# DCDC_ACCUMULATOR.net
KiCad netlist of a schematic drawn in EAGLE
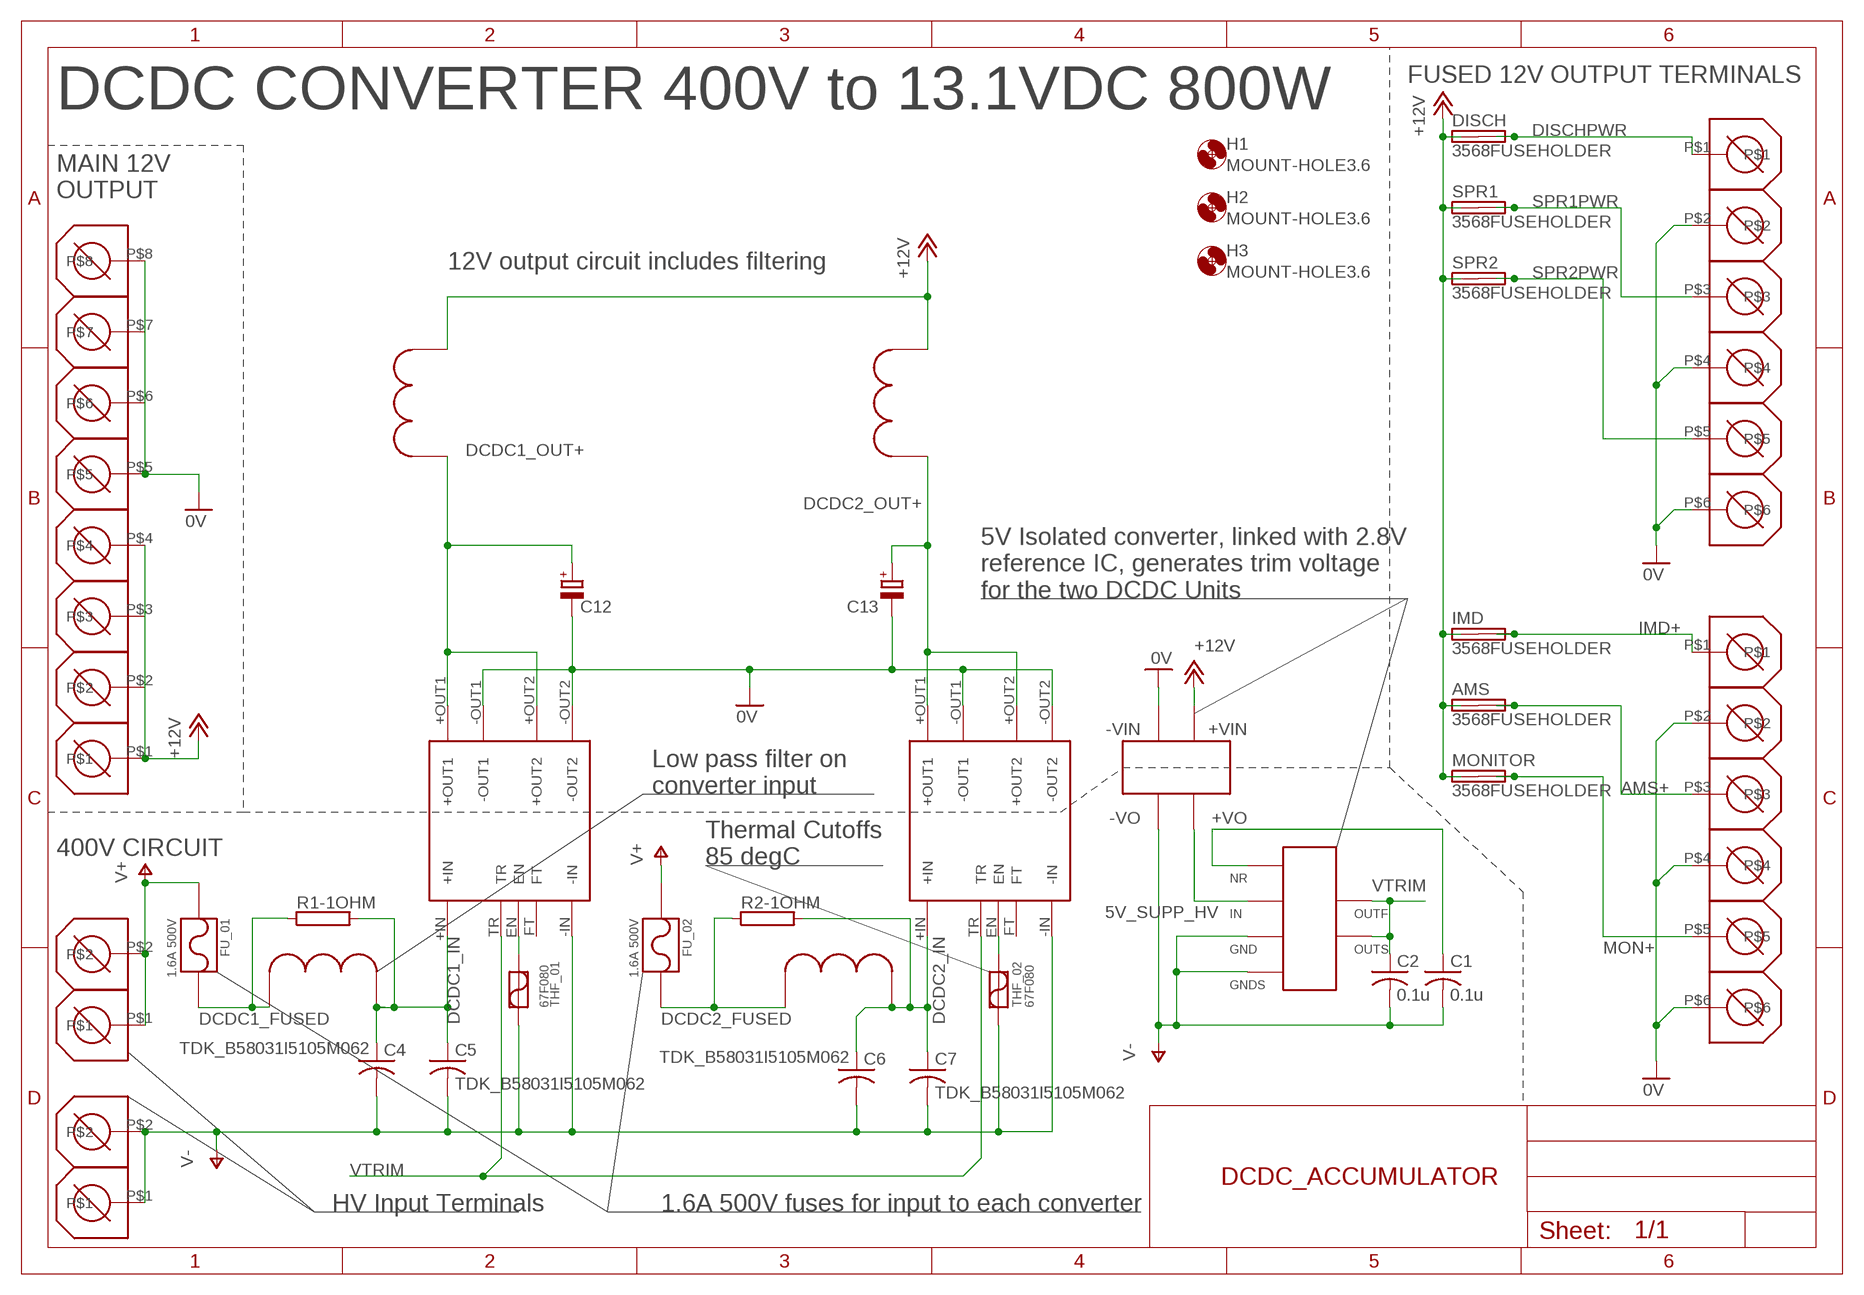
[diagram p0: schematic, sheet 1]

(export (version "E")
  (design (tool "Eeschema 10.0.6"))
  (components
    (comp (ref "AMS")
      (value "3568FUSEHOLDER")
      (footprint "eagle-import:3568")
      (libsource (lib "eagle-import") (part "3568FUSEHOLDER"))
    )
    (comp (ref "C1")
      (value "0.1u")
      (footprint "eagle-import:C0805")
      (libsource (lib "eagle-import") (part "C-USC0805"))
    )
    (comp (ref "C2")
      (value "0.1u")
      (footprint "eagle-import:C0805")
      (libsource (lib "eagle-import") (part "C-USC0805"))
    )
    (comp (ref "C4")
      (value "TDK_B58031I5105M062")
      (footprint "eagle-import:TDK_CERALINK_USTYLE")
      (libsource (lib "eagle-import") (part "TDK_B58031I5105M062"))
    )
    (comp (ref "C5")
      (value "TDK_B58031I5105M062")
      (footprint "eagle-import:TDK_CERALINK_USTYLE")
      (libsource (lib "eagle-import") (part "TDK_B58031I5105M062"))
    )
    (comp (ref "C6")
      (value "TDK_B58031I5105M062")
      (footprint "eagle-import:TDK_CERALINK_USTYLE")
      (libsource (lib "eagle-import") (part "TDK_B58031I5105M062"))
    )
    (comp (ref "C7")
      (value "TDK_B58031I5105M062")
      (footprint "eagle-import:TDK_CERALINK_USTYLE")
      (libsource (lib "eagle-import") (part "TDK_B58031I5105M062"))
    )
    (comp (ref "C12")
      (value "CPOL-EUE7.5-16")
      (footprint "eagle-import:E7,5-16")
      (libsource (lib "eagle-import") (part "CPOL-EUE7.5-16"))
    )
    (comp (ref "C13")
      (value "CPOL-EUE7.5-16")
      (footprint "eagle-import:E7,5-16")
      (libsource (lib "eagle-import") (part "CPOL-EUE7.5-16"))
    )
    (comp (ref "DISCH")
      (value "3568FUSEHOLDER")
      (footprint "eagle-import:3568")
      (libsource (lib "eagle-import") (part "3568FUSEHOLDER"))
    )
    (comp (ref "FU_01")
      (value "1.6A 500V")
      (footprint "eagle-import:LF_885")
      (libsource (lib "eagle-import") (part "LF_885"))
    )
    (comp (ref "FU_02")
      (value "1.6A 500V")
      (footprint "eagle-import:LF_885")
      (libsource (lib "eagle-import") (part "LF_885"))
    )
    (comp (ref "H1")
      (value "MOUNT-HOLE3.6")
      (footprint "eagle-import:3,6")
      (libsource (lib "eagle-import") (part "MOUNT-HOLE3.6"))
    )
    (comp (ref "H2")
      (value "MOUNT-HOLE3.6")
      (footprint "eagle-import:3,6")
      (libsource (lib "eagle-import") (part "MOUNT-HOLE3.6"))
    )
    (comp (ref "H3")
      (value "MOUNT-HOLE3.6")
      (footprint "eagle-import:3,6")
      (libsource (lib "eagle-import") (part "MOUNT-HOLE3.6"))
    )
    (comp (ref "IMD")
      (value "3568FUSEHOLDER")
      (footprint "eagle-import:3568")
      (libsource (lib "eagle-import") (part "3568FUSEHOLDER"))
    )
    (comp (ref "MONITOR")
      (value "3568FUSEHOLDER")
      (footprint "eagle-import:3568")
      (libsource (lib "eagle-import") (part "3568FUSEHOLDER"))
    )
    (comp (ref "R1-1OHM")
      (value "RMG100-V")
      (footprint "eagle-import:TO-247-2V")
      (libsource (lib "eagle-import") (part "RMG100-V"))
    )
    (comp (ref "R2-1OHM")
      (value "RMG100-V")
      (footprint "eagle-import:TO-247-2V")
      (libsource (lib "eagle-import") (part "RMG100-V"))
    )
    (comp (ref "SPR1")
      (value "3568FUSEHOLDER")
      (footprint "eagle-import:3568")
      (libsource (lib "eagle-import") (part "3568FUSEHOLDER"))
    )
    (comp (ref "SPR2")
      (value "3568FUSEHOLDER")
      (footprint "eagle-import:3568")
      (libsource (lib "eagle-import") (part "3568FUSEHOLDER"))
    )
    (comp (ref "THF_01")
      (value "67F080")
      (footprint "eagle-import:TO220ACS")
      (libsource (lib "eagle-import") (part "67F080"))
    )
    (comp (ref "THF_02")
      (value "67F080")
      (footprint "eagle-import:TO220ACS")
      (libsource (lib "eagle-import") (part "67F080"))
    )
    (comp (ref "U$1")
      (value "DCM4623TD2J13D0T00")
      (footprint "eagle-import:VICOR_DCM4623TD2J13D0T00")
      (libsource (lib "eagle-import") (part "DCM4623TD2J13D0T00"))
    )
    (comp (ref "U$2")
      (value "P1330-102H")
      (footprint "eagle-import:P1330")
      (libsource (lib "eagle-import") (part "P1330-102H"))
    )
    (comp (ref "U$3")
      (value "MPC1250LR36C")
      (footprint "eagle-import:MPC1250LR")
      (libsource (lib "eagle-import") (part "MPC1250LR36C"))
    )
    (comp (ref "U$4")
      (value "DCM4623TD2J13D0T00")
      (footprint "eagle-import:VICOR_DCM4623TD2J13D0T00")
      (libsource (lib "eagle-import") (part "DCM4623TD2J13D0T00"))
    )
    (comp (ref "U$5")
      (value "P1330-102H")
      (footprint "eagle-import:P1330")
      (libsource (lib "eagle-import") (part "P1330-102H"))
    )
    (comp (ref "U$6")
      (value "MPC1250LR36C")
      (footprint "eagle-import:MPC1250LR")
      (libsource (lib "eagle-import") (part "MPC1250LR36C"))
    )
    (comp (ref "U$9")
      (value "MURATA_MEV1S1205SC")
      (footprint "eagle-import:MEV_7_PIN_SIP")
      (libsource (lib "eagle-import") (part "MURATA_MEV1S1205SC"))
    )
    (comp (ref "U$10")
      (value "MAXIM_MAX6126A28")
      (footprint "eagle-import:UMAX")
      (libsource (lib "eagle-import") (part "MAXIM_MAX6126A28"))
    )
    (comp (ref "U$13")
      (value "1777600_PHOENIX")
      (footprint "eagle-import:1777600_FOOT")
      (libsource (lib "eagle-import") (part "1777600_PHOENIX"))
    )
    (comp (ref "U$14")
      (value "1935200_PHOENIX")
      (footprint "eagle-import:1777587_FOOT")
      (libsource (lib "eagle-import") (part "1935200_PHOENIX"))
    )
    (comp (ref "U$15")
      (value "1935200_PHOENIX")
      (footprint "eagle-import:1777587_FOOT")
      (libsource (lib "eagle-import") (part "1935200_PHOENIX"))
    )
    (comp (ref "U$16")
      (value "282838-2_TE")
      (footprint "eagle-import:282838-2_FOOT")
      (libsource (lib "eagle-import") (part "282838-2_TE"))
    )
    (comp (ref "U$17")
      (value "282838-2_TE")
      (footprint "eagle-import:282838-2_FOOT")
      (libsource (lib "eagle-import") (part "282838-2_TE"))
    )
  )
  (nets
    (net (code "1") (name "+12V") (class "Default")
      (node (ref "AMS") (pin "L1") (pinfunction "1A_L1") (pintype "passive"))
      (node (ref "AMS") (pin "L2") (pinfunction "1B_L2") (pintype "passive"))
      (node (ref "DISCH") (pin "L1") (pinfunction "1A_L1") (pintype "passive"))
      (node (ref "DISCH") (pin "L2") (pinfunction "1B_L2") (pintype "passive"))
      (node (ref "IMD") (pin "L1") (pinfunction "1A_L1") (pintype "passive"))
      (node (ref "IMD") (pin "L2") (pinfunction "1B_L2") (pintype "passive"))
      (node (ref "MONITOR") (pin "L1") (pinfunction "1A_L1") (pintype "passive"))
      (node (ref "MONITOR") (pin "L2") (pinfunction "1B_L2") (pintype "passive"))
      (node (ref "SPR1") (pin "L1") (pinfunction "1A_L1") (pintype "passive"))
      (node (ref "SPR1") (pin "L2") (pinfunction "1B_L2") (pintype "passive"))
      (node (ref "SPR2") (pin "L1") (pinfunction "1A_L1") (pintype "passive"))
      (node (ref "SPR2") (pin "L2") (pinfunction "1B_L2") (pintype "passive"))
      (node (ref "U$13") (pin "P$1") (pinfunction "P$1_P$1") (pintype "bidirectional"))
      (node (ref "U$13") (pin "P$2") (pinfunction "P$2_P$2") (pintype "bidirectional"))
      (node (ref "U$13") (pin "P$3") (pinfunction "P$3_P$3") (pintype "bidirectional"))
      (node (ref "U$13") (pin "P$4") (pinfunction "P$4_P$4") (pintype "bidirectional"))
      (node (ref "U$3") (pin "P$2") (pinfunction "P$2_P$2") (pintype "bidirectional"))
      (node (ref "U$6") (pin "P$2") (pinfunction "P$2_P$2") (pintype "bidirectional"))
      (node (ref "U$9") (pin "+VIN") (pinfunction "+VIN_+VIN") (pintype "bidirectional"))
    )
    (net (code "2") (name "/5V_SUPP_HV") (class "Default")
      (node (ref "U$10") (pin "2") (pinfunction "IN_2") (pintype "bidirectional"))
      (node (ref "U$9") (pin "+VOUT") (pinfunction "+VO_+VOUT") (pintype "bidirectional"))
    )
    (net (code "3") (name "/AMS+") (class "Default")
      (node (ref "AMS") (pin "R1") (pinfunction "2A_R1") (pintype "passive"))
      (node (ref "AMS") (pin "R2") (pinfunction "2B_R2") (pintype "passive"))
      (node (ref "U$15") (pin "P$3") (pinfunction "P$3_P$3") (pintype "bidirectional"))
    )
    (net (code "4") (name "/DCDC1_FUSED") (class "Default")
      (node (ref "FU_01") (pin "P$2") (pinfunction "P$2_P$2") (pintype "bidirectional"))
      (node (ref "R1-1OHM") (pin "1") (pinfunction "1_1") (pintype "passive"))
      (node (ref "U$2") (pin "P$1") (pinfunction "P$1_P$1") (pintype "bidirectional"))
    )
    (net (code "5") (name "/DCDC1_IN") (class "Default")
      (node (ref "C4") (pin "P$1") (pinfunction "1_P$1") (pintype "passive"))
      (node (ref "C5") (pin "P$1") (pinfunction "1_P$1") (pintype "passive"))
      (node (ref "R1-1OHM") (pin "2") (pinfunction "2_2") (pintype "passive"))
      (node (ref "U$1") (pin "+IN") (pinfunction "+IN_+IN") (pintype "bidirectional"))
      (node (ref "U$2") (pin "P$2") (pinfunction "P$2_P$2") (pintype "bidirectional"))
    )
    (net (code "6") (name "/DCDC1_OUT+") (class "Default")
      (node (ref "C12") (pin "+") (pinfunction "+_+") (pintype "passive"))
      (node (ref "U$1") (pin "+OUT1") (pinfunction "+OUT1_+OUT1") (pintype "bidirectional"))
      (node (ref "U$1") (pin "+OUT2") (pinfunction "+OUT2_+OUT2") (pintype "bidirectional"))
      (node (ref "U$3") (pin "P$1") (pinfunction "P$1_P$1") (pintype "bidirectional"))
    )
    (net (code "7") (name "/DCDC2_FUSED") (class "Default")
      (node (ref "FU_02") (pin "P$2") (pinfunction "P$2_P$2") (pintype "bidirectional"))
      (node (ref "R2-1OHM") (pin "1") (pinfunction "1_1") (pintype "passive"))
      (node (ref "U$5") (pin "P$1") (pinfunction "P$1_P$1") (pintype "bidirectional"))
    )
    (net (code "8") (name "/DCDC2_IN") (class "Default")
      (node (ref "C6") (pin "P$1") (pinfunction "1_P$1") (pintype "passive"))
      (node (ref "C7") (pin "P$1") (pinfunction "1_P$1") (pintype "passive"))
      (node (ref "R2-1OHM") (pin "2") (pinfunction "2_2") (pintype "passive"))
      (node (ref "U$4") (pin "+IN") (pinfunction "+IN_+IN") (pintype "bidirectional"))
      (node (ref "U$5") (pin "P$2") (pinfunction "P$2_P$2") (pintype "bidirectional"))
    )
    (net (code "9") (name "/DCDC2_OUT+") (class "Default")
      (node (ref "C13") (pin "+") (pinfunction "+_+") (pintype "passive"))
      (node (ref "U$4") (pin "+OUT1") (pinfunction "+OUT1_+OUT1") (pintype "bidirectional"))
      (node (ref "U$4") (pin "+OUT2") (pinfunction "+OUT2_+OUT2") (pintype "bidirectional"))
      (node (ref "U$6") (pin "P$1") (pinfunction "P$1_P$1") (pintype "bidirectional"))
    )
    (net (code "10") (name "/DISCHPWR") (class "Default")
      (node (ref "DISCH") (pin "R1") (pinfunction "2A_R1") (pintype "passive"))
      (node (ref "DISCH") (pin "R2") (pinfunction "2B_R2") (pintype "passive"))
      (node (ref "U$14") (pin "P$1") (pinfunction "P$1_P$1") (pintype "bidirectional"))
    )
    (net (code "11") (name "/IMD+") (class "Default")
      (node (ref "IMD") (pin "R1") (pinfunction "2A_R1") (pintype "passive"))
      (node (ref "IMD") (pin "R2") (pinfunction "2B_R2") (pintype "passive"))
      (node (ref "U$15") (pin "P$1") (pinfunction "P$1_P$1") (pintype "bidirectional"))
    )
    (net (code "12") (name "/MON+") (class "Default")
      (node (ref "MONITOR") (pin "R1") (pinfunction "2A_R1") (pintype "passive"))
      (node (ref "MONITOR") (pin "R2") (pinfunction "2B_R2") (pintype "passive"))
      (node (ref "U$15") (pin "P$5") (pinfunction "P$5_P$5") (pintype "bidirectional"))
    )
    (net (code "13") (name "/SPR1PWR") (class "Default")
      (node (ref "SPR1") (pin "R1") (pinfunction "2A_R1") (pintype "passive"))
      (node (ref "SPR1") (pin "R2") (pinfunction "2B_R2") (pintype "passive"))
      (node (ref "U$14") (pin "P$3") (pinfunction "P$3_P$3") (pintype "bidirectional"))
    )
    (net (code "14") (name "/SPR2PWR") (class "Default")
      (node (ref "SPR2") (pin "R1") (pinfunction "2A_R1") (pintype "passive"))
      (node (ref "SPR2") (pin "R2") (pinfunction "2B_R2") (pintype "passive"))
      (node (ref "U$14") (pin "P$5") (pinfunction "P$5_P$5") (pintype "bidirectional"))
    )
    (net (code "15") (name "/VTRIM") (class "Default")
      (node (ref "C2") (pin "1") (pinfunction "1_1") (pintype "passive"))
      (node (ref "U$1") (pin "TR") (pinfunction "TR_TR") (pintype "bidirectional"))
      (node (ref "U$10") (pin "6") (pinfunction "OUTS_6") (pintype "bidirectional"))
      (node (ref "U$10") (pin "7") (pinfunction "OUTF_7") (pintype "bidirectional"))
      (node (ref "U$4") (pin "TR") (pinfunction "TR_TR") (pintype "bidirectional"))
    )
    (net (code "16") (name "0V") (class "Default")
      (node (ref "C12") (pin "-") (pinfunction "-_-") (pintype "passive"))
      (node (ref "C13") (pin "-") (pinfunction "-_-") (pintype "passive"))
      (node (ref "U$1") (pin "-OUT1") (pinfunction "-OUT1_-OUT1") (pintype "bidirectional"))
      (node (ref "U$1") (pin "-OUT2") (pinfunction "-OUT2_-OUT2") (pintype "bidirectional"))
      (node (ref "U$13") (pin "P$5") (pinfunction "P$5_P$5") (pintype "bidirectional"))
      (node (ref "U$13") (pin "P$6") (pinfunction "P$6_P$6") (pintype "bidirectional"))
      (node (ref "U$13") (pin "P$7") (pinfunction "P$7_P$7") (pintype "bidirectional"))
      (node (ref "U$13") (pin "P$8") (pinfunction "P$8_P$8") (pintype "bidirectional"))
      (node (ref "U$14") (pin "P$2") (pinfunction "P$2_P$2") (pintype "bidirectional"))
      (node (ref "U$14") (pin "P$4") (pinfunction "P$4_P$4") (pintype "bidirectional"))
      (node (ref "U$14") (pin "P$6") (pinfunction "P$6_P$6") (pintype "bidirectional"))
      (node (ref "U$15") (pin "P$2") (pinfunction "P$2_P$2") (pintype "bidirectional"))
      (node (ref "U$15") (pin "P$4") (pinfunction "P$4_P$4") (pintype "bidirectional"))
      (node (ref "U$15") (pin "P$6") (pinfunction "P$6_P$6") (pintype "bidirectional"))
      (node (ref "U$4") (pin "-OUT1") (pinfunction "-OUT1_-OUT1") (pintype "bidirectional"))
      (node (ref "U$4") (pin "-OUT2") (pinfunction "-OUT2_-OUT2") (pintype "bidirectional"))
      (node (ref "U$9") (pin "-VIN") (pinfunction "-VIN_-VIN") (pintype "bidirectional"))
    )
    (net (code "17") (name "Net-(THF_01-P$2)") (class "Default")
      (node (ref "THF_01") (pin "C") (pinfunction "P$2_C") (pintype "bidirectional"))
      (node (ref "U$1") (pin "EN") (pinfunction "EN_EN") (pintype "bidirectional"))
    )
    (net (code "18") (name "Net-(THF_02-P$2)") (class "Default")
      (node (ref "THF_02") (pin "C") (pinfunction "P$2_C") (pintype "bidirectional"))
      (node (ref "U$4") (pin "EN") (pinfunction "EN_EN") (pintype "bidirectional"))
    )
    (net (code "19") (name "Net-(U$10-NR)") (class "Default")
      (node (ref "C1") (pin "1") (pinfunction "1_1") (pintype "passive"))
      (node (ref "U$10") (pin "1") (pinfunction "NR_1") (pintype "bidirectional"))
    )
    (net (code "20") (name "V+") (class "Default")
      (node (ref "FU_01") (pin "P$1") (pinfunction "P$1_P$1") (pintype "bidirectional"))
      (node (ref "FU_02") (pin "P$1") (pinfunction "P$1_P$1") (pintype "bidirectional"))
      (node (ref "U$16") (pin "P$1") (pinfunction "P$1_P$1") (pintype "bidirectional"))
      (node (ref "U$16") (pin "P$2") (pinfunction "P$2_P$2") (pintype "bidirectional"))
    )
    (net (code "21") (name "V-") (class "Default")
      (node (ref "C1") (pin "2") (pinfunction "2_2") (pintype "passive"))
      (node (ref "C2") (pin "2") (pinfunction "2_2") (pintype "passive"))
      (node (ref "C4") (pin "P$2") (pinfunction "2_P$2") (pintype "passive"))
      (node (ref "C5") (pin "P$2") (pinfunction "2_P$2") (pintype "passive"))
      (node (ref "C6") (pin "P$2") (pinfunction "2_P$2") (pintype "passive"))
      (node (ref "C7") (pin "P$2") (pinfunction "2_P$2") (pintype "passive"))
      (node (ref "THF_01") (pin "A") (pinfunction "P$1_A") (pintype "bidirectional"))
      (node (ref "THF_02") (pin "A") (pinfunction "P$1_A") (pintype "bidirectional"))
      (node (ref "U$1") (pin "-IN") (pinfunction "-IN_-IN") (pintype "bidirectional"))
      (node (ref "U$10") (pin "3") (pinfunction "GND_3") (pintype "bidirectional"))
      (node (ref "U$10") (pin "4") (pinfunction "GNDS_4") (pintype "bidirectional"))
      (node (ref "U$17") (pin "P$1") (pinfunction "P$1_P$1") (pintype "bidirectional"))
      (node (ref "U$17") (pin "P$2") (pinfunction "P$2_P$2") (pintype "bidirectional"))
      (node (ref "U$4") (pin "-IN") (pinfunction "-IN_-IN") (pintype "bidirectional"))
      (node (ref "U$9") (pin "-VOUT") (pinfunction "-VO_-VOUT") (pintype "bidirectional"))
    )
    (net (code "22") (name "unconnected-(U$1-PadFT)") (class "Default")
      (node (ref "U$1") (pin "FT") (pinfunction "FT_FT") (pintype "bidirectional"))
    )
    (net (code "23") (name "unconnected-(U$4-PadFT)") (class "Default")
      (node (ref "U$4") (pin "FT") (pinfunction "FT_FT") (pintype "bidirectional"))
    )
  )
)
